# ws.net
KiCad netlist of a schematic drawn in EAGLE
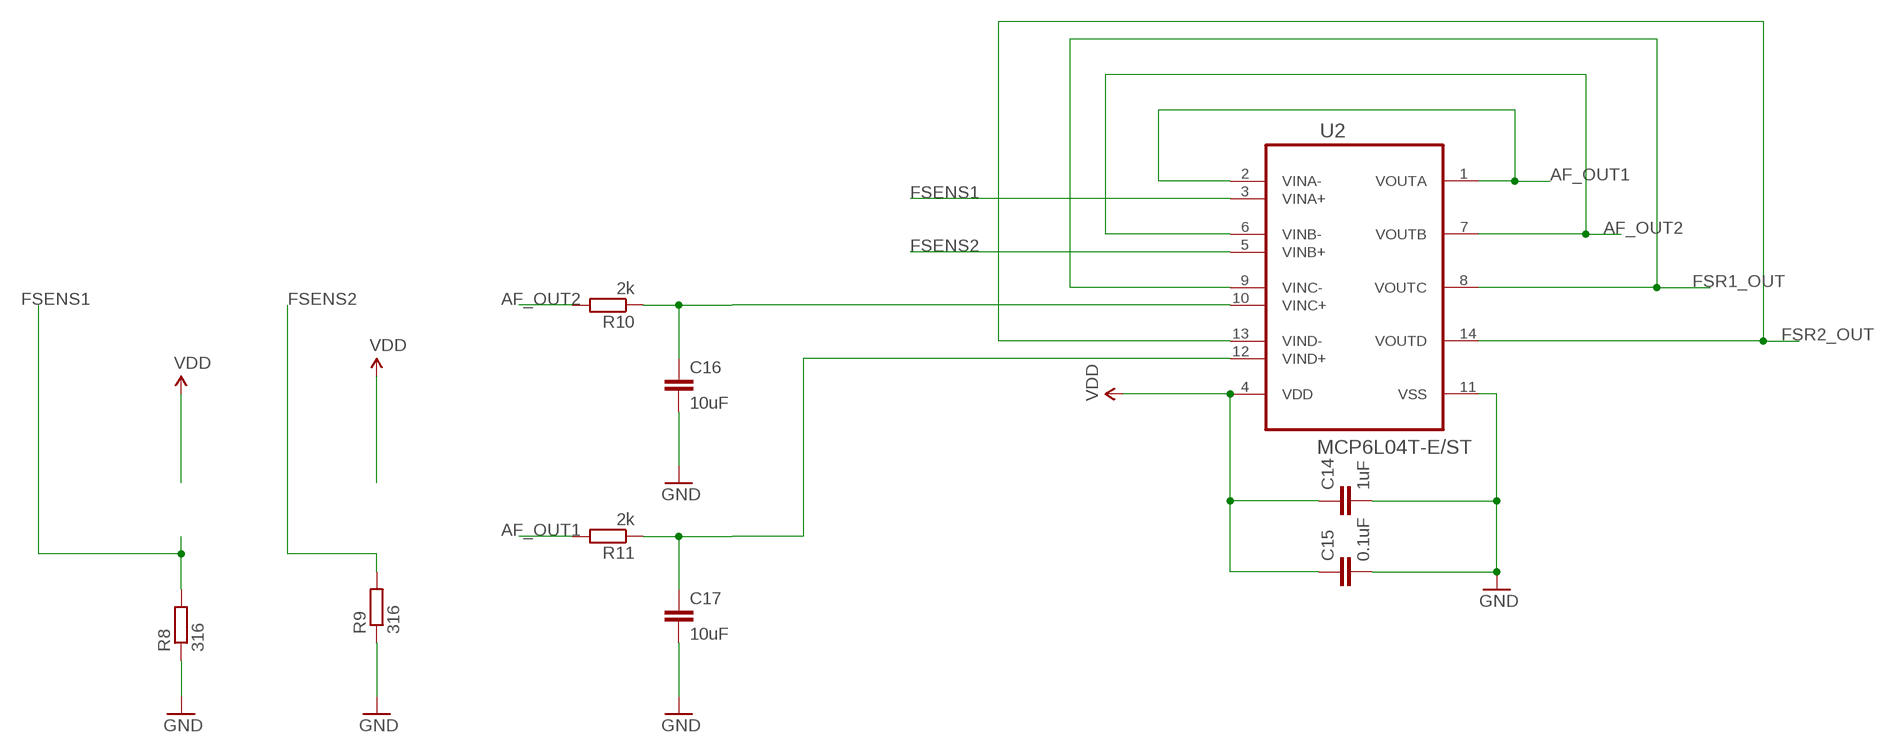
[diagram p0: schematic, sheet 1]

(export (version "E")
  (design (tool "Eeschema 10.0.6"))
  (components
    (comp (ref "C14")
      (value "1uF")
      (footprint "eagle-import:C0402")
      (libsource (lib "eagle-import") (part "C-EUC0402"))
    )
    (comp (ref "C15")
      (value "0.1uF")
      (footprint "eagle-import:C0402")
      (libsource (lib "eagle-import") (part "C-EUC0402"))
    )
    (comp (ref "C16")
      (value "10uF")
      (footprint "eagle-import:C0402")
      (libsource (lib "eagle-import") (part "C-EUC0402"))
    )
    (comp (ref "C17")
      (value "10uF")
      (footprint "eagle-import:C0402")
      (libsource (lib "eagle-import") (part "C-EUC0402"))
    )
    (comp (ref "R8")
      (value "316")
      (footprint "eagle-import:R0402")
      (libsource (lib "eagle-import") (part "R-EU_R0402"))
    )
    (comp (ref "R9")
      (value "316")
      (footprint "eagle-import:R0402")
      (libsource (lib "eagle-import") (part "R-EU_R0402"))
    )
    (comp (ref "R10")
      (value "2k")
      (footprint "eagle-import:R0402")
      (libsource (lib "eagle-import") (part "R-EU_R0402"))
    )
    (comp (ref "R11")
      (value "2k")
      (footprint "eagle-import:R0402")
      (libsource (lib "eagle-import") (part "R-EU_R0402"))
    )
    (comp (ref "U2")
      (value "MCP6L04T-E/ST")
      (footprint "eagle-import:SOP65P640X120-14N")
      (libsource (lib "eagle-import") (part "MCP6L04T-E/ST"))
    )
  )
  (nets
    (net (code "1") (name "/AF_OUT1") (class "Default")
      (node (ref "R11") (pin "2") (pinfunction "2_2") (pintype "passive"))
      (node (ref "U2") (pin "1") (pinfunction "VOUTA_1") (pintype "passive"))
      (node (ref "U2") (pin "2") (pinfunction "VINA-_2") (pintype "passive"))
    )
    (net (code "2") (name "/AF_OUT2") (class "Default")
      (node (ref "R10") (pin "2") (pinfunction "2_2") (pintype "passive"))
      (node (ref "U2") (pin "6") (pinfunction "VINB-_6") (pintype "passive"))
      (node (ref "U2") (pin "7") (pinfunction "VOUTB_7") (pintype "passive"))
    )
    (net (code "3") (name "/FSENS1") (class "Default")
      (node (ref "R8") (pin "2") (pinfunction "2_2") (pintype "passive"))
      (node (ref "U2") (pin "3") (pinfunction "VINA+_3") (pintype "passive"))
    )
    (net (code "4") (name "/FSENS2") (class "Default")
      (node (ref "R9") (pin "2") (pinfunction "2_2") (pintype "passive"))
      (node (ref "U2") (pin "5") (pinfunction "VINB+_5") (pintype "passive"))
    )
    (net (code "5") (name "/FSR1_OUT") (class "Default")
      (node (ref "U2") (pin "8") (pinfunction "VOUTC_8") (pintype "passive"))
      (node (ref "U2") (pin "9") (pinfunction "VINC-_9") (pintype "passive"))
    )
    (net (code "6") (name "/FSR2_OUT") (class "Default")
      (node (ref "U2") (pin "13") (pinfunction "VIND-_13") (pintype "passive"))
      (node (ref "U2") (pin "14") (pinfunction "VOUTD_14") (pintype "passive"))
    )
    (net (code "7") (name "GND") (class "Default")
      (node (ref "C14") (pin "2") (pinfunction "2_2") (pintype "passive"))
      (node (ref "C15") (pin "2") (pinfunction "2_2") (pintype "passive"))
      (node (ref "C16") (pin "2") (pinfunction "2_2") (pintype "passive"))
      (node (ref "C17") (pin "2") (pinfunction "2_2") (pintype "passive"))
      (node (ref "R8") (pin "1") (pinfunction "1_1") (pintype "passive"))
      (node (ref "R9") (pin "1") (pinfunction "1_1") (pintype "passive"))
      (node (ref "U2") (pin "11") (pinfunction "VSS_11") (pintype "power_in"))
    )
    (net (code "8") (name "Net-(U2-VINC+)") (class "Default")
      (node (ref "C16") (pin "1") (pinfunction "1_1") (pintype "passive"))
      (node (ref "R10") (pin "1") (pinfunction "1_1") (pintype "passive"))
      (node (ref "U2") (pin "10") (pinfunction "VINC+_10") (pintype "passive"))
    )
    (net (code "9") (name "Net-(U2-VIND+)") (class "Default")
      (node (ref "C17") (pin "1") (pinfunction "1_1") (pintype "passive"))
      (node (ref "R11") (pin "1") (pinfunction "1_1") (pintype "passive"))
      (node (ref "U2") (pin "12") (pinfunction "VIND+_12") (pintype "passive"))
    )
    (net (code "10") (name "VDD") (class "Default")
      (node (ref "C14") (pin "1") (pinfunction "1_1") (pintype "passive"))
      (node (ref "C15") (pin "1") (pinfunction "1_1") (pintype "passive"))
      (node (ref "U2") (pin "4") (pinfunction "VDD_4") (pintype "power_in"))
    )
  )
)
